# goodfet42.net
KiCad netlist of a schematic drawn in EAGLE
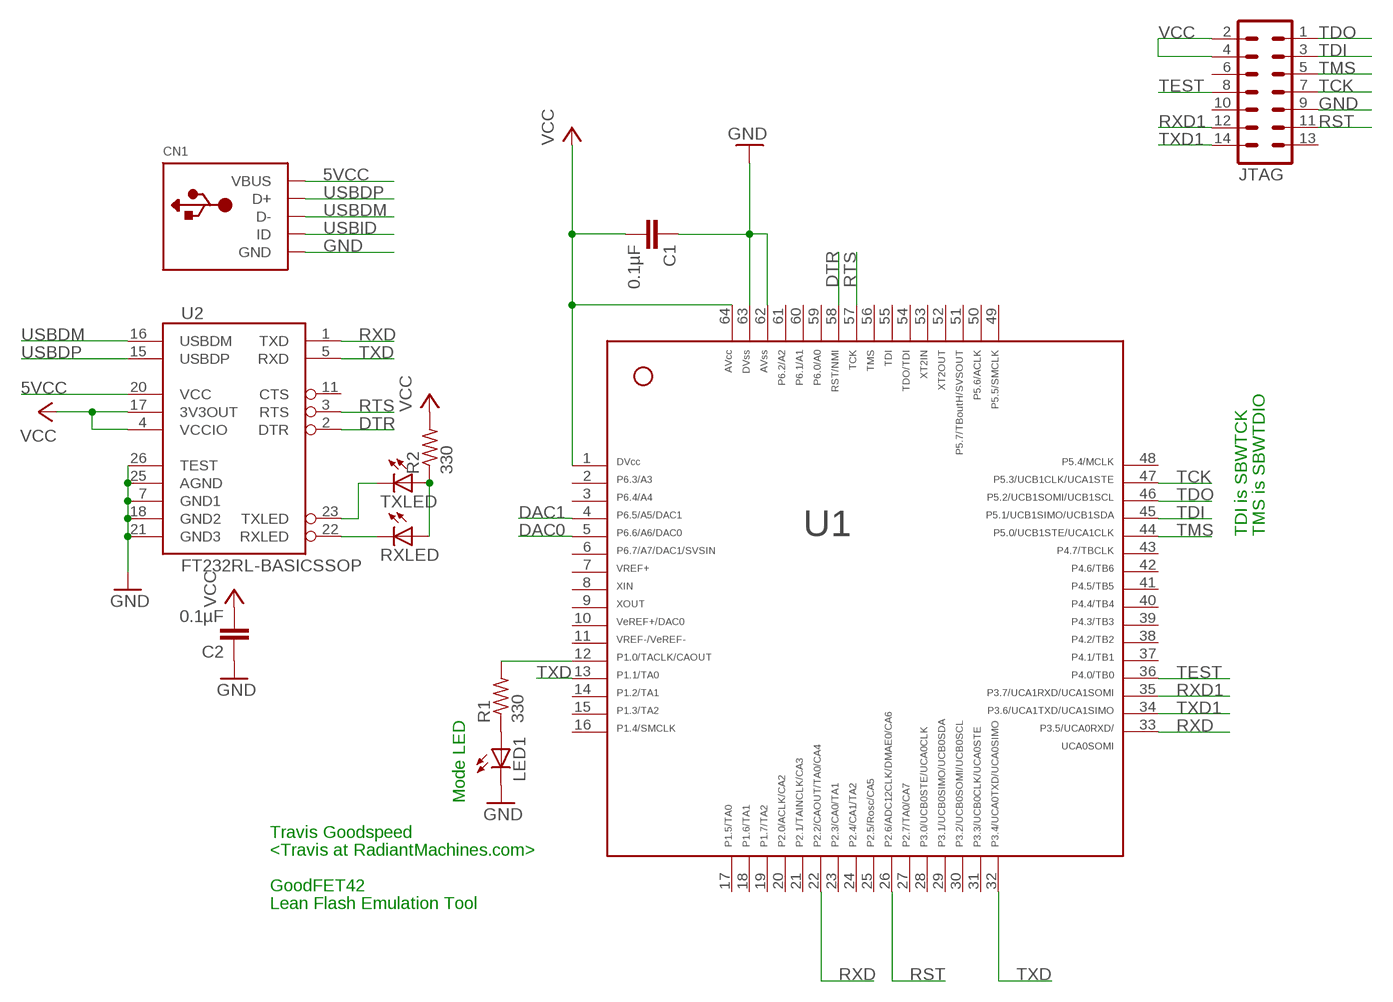
[diagram p0: schematic, sheet 1]

(export (version "E")
  (design (tool "Eeschema 10.0.6"))
  (components
    (comp (ref "C1")
      (value "0.1µF")
      (footprint "eagle-import:C0603")
      (libsource (lib "eagle-import") (part "C-EUC0603"))
    )
    (comp (ref "C2")
      (value "0.1µF")
      (footprint "eagle-import:C0603")
      (libsource (lib "eagle-import") (part "C-EUC0603"))
    )
    (comp (ref "CN1")
      (value "USBMINIB")
      (footprint "eagle-import:USB-MINIB")
      (libsource (lib "eagle-import") (part "USBMINIB"))
    )
    (comp (ref "JTAG")
      (value "MA07-2")
      (footprint "eagle-import:MA07-2")
      (libsource (lib "eagle-import") (part "MA07-2"))
    )
    (comp (ref "LED1")
      (value "LEDCHIP-LED0603")
      (footprint "eagle-import:CHIP-LED0603")
      (libsource (lib "eagle-import") (part "LEDCHIP-LED0603"))
    )
    (comp (ref "R1")
      (value "330")
      (footprint "eagle-import:R0603")
      (libsource (lib "eagle-import") (part "R-US_R0603"))
    )
    (comp (ref "R2")
      (value "330")
      (footprint "eagle-import:R0603")
      (libsource (lib "eagle-import") (part "R-US_R0603"))
    )
    (comp (ref "RXLED")
      (value "LEDCHIP-LED0603")
      (footprint "eagle-import:CHIP-LED0603")
      (libsource (lib "eagle-import") (part "LEDCHIP-LED0603"))
    )
    (comp (ref "TXLED")
      (value "LEDCHIP-LED0603")
      (footprint "eagle-import:CHIP-LED0603")
      (libsource (lib "eagle-import") (part "LEDCHIP-LED0603"))
    )
    (comp (ref "U1")
      (value "F261X---PM64")
      (footprint "eagle-import:PM_PAG64")
      (libsource (lib "eagle-import") (part "F261X---PM64"))
    )
    (comp (ref "U2")
      (value "FT232RL-BASICSSOP")
      (footprint "eagle-import:SSOP28DB")
      (libsource (lib "eagle-import") (part "FT232RL-BASICSSOP"))
    )
  )
  (nets
    (net (code "1") (name "/5VCC") (class "Default")
      (node (ref "CN1") (pin "VBUS") (pinfunction "VBUS_VBUS") (pintype "power_in"))
      (node (ref "U2") (pin "20") (pinfunction "VCC_20") (pintype "power_in"))
    )
    (net (code "2") (name "/DAC0") (class "Default")
      (node (ref "U1") (pin "5") (pinfunction "5_5") (pintype "bidirectional"))
    )
    (net (code "3") (name "/DAC1") (class "Default")
      (node (ref "U1") (pin "4") (pinfunction "4_4") (pintype "bidirectional"))
    )
    (net (code "4") (name "/DTR") (class "Default")
      (node (ref "U1") (pin "58") (pinfunction "58_58") (pintype "input"))
      (node (ref "U2") (pin "2") (pinfunction "DTR_2") (pintype "bidirectional"))
    )
    (net (code "5") (name "/RST") (class "Default")
      (node (ref "JTAG") (pin "11") (pinfunction "11_11") (pintype "passive"))
      (node (ref "U1") (pin "26") (pinfunction "26_26") (pintype "bidirectional"))
    )
    (net (code "6") (name "/RTS") (class "Default")
      (node (ref "U1") (pin "57") (pinfunction "57_57") (pintype "input"))
      (node (ref "U2") (pin "3") (pinfunction "RTS_3") (pintype "bidirectional"))
    )
    (net (code "7") (name "/RXD") (class "Default")
      (node (ref "U1") (pin "22") (pinfunction "22_22") (pintype "bidirectional"))
      (node (ref "U1") (pin "33") (pinfunction "33_33") (pintype "bidirectional"))
      (node (ref "U2") (pin "1") (pinfunction "TXD_1") (pintype "output"))
    )
    (net (code "8") (name "/RXD1") (class "Default")
      (node (ref "JTAG") (pin "12") (pinfunction "12_12") (pintype "passive"))
      (node (ref "U1") (pin "35") (pinfunction "35_35") (pintype "bidirectional"))
    )
    (net (code "9") (name "/TCK") (class "Default")
      (node (ref "JTAG") (pin "7") (pinfunction "7_7") (pintype "passive"))
      (node (ref "U1") (pin "47") (pinfunction "47_47") (pintype "bidirectional"))
    )
    (net (code "10") (name "/TDI") (class "Default")
      (node (ref "JTAG") (pin "3") (pinfunction "3_3") (pintype "passive"))
      (node (ref "U1") (pin "45") (pinfunction "45_45") (pintype "bidirectional"))
    )
    (net (code "11") (name "/TDO") (class "Default")
      (node (ref "JTAG") (pin "1") (pinfunction "1_1") (pintype "passive"))
      (node (ref "U1") (pin "46") (pinfunction "46_46") (pintype "bidirectional"))
    )
    (net (code "12") (name "/TEST") (class "Default")
      (node (ref "JTAG") (pin "8") (pinfunction "8_8") (pintype "passive"))
      (node (ref "U1") (pin "36") (pinfunction "36_36") (pintype "output"))
    )
    (net (code "13") (name "/TMS") (class "Default")
      (node (ref "JTAG") (pin "5") (pinfunction "5_5") (pintype "passive"))
      (node (ref "U1") (pin "44") (pinfunction "44_44") (pintype "bidirectional"))
    )
    (net (code "14") (name "/TXD") (class "Default")
      (node (ref "U1") (pin "13") (pinfunction "13_13") (pintype "bidirectional"))
      (node (ref "U1") (pin "32") (pinfunction "32_32") (pintype "bidirectional"))
      (node (ref "U2") (pin "5") (pinfunction "RXD_5") (pintype "input"))
    )
    (net (code "15") (name "/TXD1") (class "Default")
      (node (ref "JTAG") (pin "14") (pinfunction "14_14") (pintype "passive"))
      (node (ref "U1") (pin "34") (pinfunction "34_34") (pintype "bidirectional"))
    )
    (net (code "16") (name "/USBDM") (class "Default")
      (node (ref "CN1") (pin "D-") (pinfunction "D-_D-") (pintype "bidirectional"))
      (node (ref "U2") (pin "16") (pinfunction "USBDM_16") (pintype "bidirectional"))
    )
    (net (code "17") (name "/USBDP") (class "Default")
      (node (ref "CN1") (pin "D+") (pinfunction "D+_D+") (pintype "bidirectional"))
      (node (ref "U2") (pin "15") (pinfunction "USBDP_15") (pintype "bidirectional"))
    )
    (net (code "18") (name "/USBID") (class "Default")
      (node (ref "CN1") (pin "ID") (pinfunction "ID_ID") (pintype "bidirectional"))
    )
    (net (code "19") (name "GND") (class "Default")
      (node (ref "C1") (pin "1") (pinfunction "1_1") (pintype "passive"))
      (node (ref "C2") (pin "1") (pinfunction "1_1") (pintype "passive"))
      (node (ref "CN1") (pin "GND") (pinfunction "GND_GND") (pintype "power_in"))
      (node (ref "JTAG") (pin "9") (pinfunction "9_9") (pintype "passive"))
      (node (ref "LED1") (pin "C") (pinfunction "C_C") (pintype "passive"))
      (node (ref "U1") (pin "62") (pinfunction "62_62") (pintype "power_in"))
      (node (ref "U1") (pin "63") (pinfunction "63_63") (pintype "power_in"))
      (node (ref "U2") (pin "18") (pinfunction "GND2_18") (pintype "power_in"))
      (node (ref "U2") (pin "21") (pinfunction "GND3_21") (pintype "power_in"))
      (node (ref "U2") (pin "25") (pinfunction "AGND_25") (pintype "power_in"))
      (node (ref "U2") (pin "26") (pinfunction "TEST_26") (pintype "input"))
      (node (ref "U2") (pin "7") (pinfunction "GND1_7") (pintype "power_in"))
    )
    (net (code "20") (name "Net-(LED1-PadA)") (class "Default")
      (node (ref "LED1") (pin "A") (pinfunction "A_A") (pintype "passive"))
      (node (ref "R1") (pin "1") (pinfunction "1_1") (pintype "passive"))
    )
    (net (code "21") (name "Net-(R1-Pad2)") (class "Default")
      (node (ref "R1") (pin "2") (pinfunction "2_2") (pintype "passive"))
      (node (ref "U1") (pin "12") (pinfunction "12_12") (pintype "bidirectional"))
    )
    (net (code "22") (name "Net-(R2-Pad1)") (class "Default")
      (node (ref "R2") (pin "1") (pinfunction "1_1") (pintype "passive"))
      (node (ref "RXLED") (pin "A") (pinfunction "A_A") (pintype "passive"))
      (node (ref "TXLED") (pin "A") (pinfunction "A_A") (pintype "passive"))
    )
    (net (code "23") (name "Net-(U2-RXLED)") (class "Default")
      (node (ref "RXLED") (pin "C") (pinfunction "C_C") (pintype "passive"))
      (node (ref "U2") (pin "22") (pinfunction "RXLED_22") (pintype "bidirectional"))
    )
    (net (code "24") (name "Net-(U2-TXLED)") (class "Default")
      (node (ref "TXLED") (pin "C") (pinfunction "C_C") (pintype "passive"))
      (node (ref "U2") (pin "23") (pinfunction "TXLED_23") (pintype "bidirectional"))
    )
    (net (code "25") (name "VCC") (class "Default")
      (node (ref "C1") (pin "2") (pinfunction "2_2") (pintype "passive"))
      (node (ref "C2") (pin "2") (pinfunction "2_2") (pintype "passive"))
      (node (ref "JTAG") (pin "2") (pinfunction "2_2") (pintype "passive"))
      (node (ref "JTAG") (pin "4") (pinfunction "4_4") (pintype "passive"))
      (node (ref "R2") (pin "2") (pinfunction "2_2") (pintype "passive"))
      (node (ref "U1") (pin "1") (pinfunction "1_1") (pintype "power_in"))
      (node (ref "U1") (pin "64") (pinfunction "64_64") (pintype "power_in"))
      (node (ref "U2") (pin "17") (pinfunction "3V3OUT_17") (pintype "output"))
      (node (ref "U2") (pin "4") (pinfunction "VCCIO_4") (pintype "power_in"))
    )
    (net (code "26") (name "unconnected-(JTAG-Pad6)") (class "Default")
      (node (ref "JTAG") (pin "6") (pinfunction "6_6") (pintype "passive"))
    )
    (net (code "27") (name "unconnected-(JTAG-Pad10)") (class "Default")
      (node (ref "JTAG") (pin "10") (pinfunction "10_10") (pintype "passive"))
    )
    (net (code "28") (name "unconnected-(JTAG-Pad13)") (class "Default")
      (node (ref "JTAG") (pin "13") (pinfunction "13_13") (pintype "passive"))
    )
    (net (code "29") (name "unconnected-(U1-Pad2)") (class "Default")
      (node (ref "U1") (pin "2") (pinfunction "2_2") (pintype "bidirectional"))
    )
    (net (code "30") (name "unconnected-(U1-Pad3)") (class "Default")
      (node (ref "U1") (pin "3") (pinfunction "3_3") (pintype "bidirectional"))
    )
    (net (code "31") (name "unconnected-(U1-Pad6)") (class "Default")
      (node (ref "U1") (pin "6") (pinfunction "6_6") (pintype "bidirectional"))
    )
    (net (code "32") (name "unconnected-(U1-Pad7)") (class "Default")
      (node (ref "U1") (pin "7") (pinfunction "7_7") (pintype "output"))
    )
    (net (code "33") (name "unconnected-(U1-Pad8)") (class "Default")
      (node (ref "U1") (pin "8") (pinfunction "8_8") (pintype "input"))
    )
    (net (code "34") (name "unconnected-(U1-Pad9)") (class "Default")
      (node (ref "U1") (pin "9") (pinfunction "9_9") (pintype "output"))
    )
    (net (code "35") (name "unconnected-(U1-Pad10)") (class "Default")
      (node (ref "U1") (pin "10") (pinfunction "10_10") (pintype "bidirectional"))
    )
    (net (code "36") (name "unconnected-(U1-Pad11)") (class "Default")
      (node (ref "U1") (pin "11") (pinfunction "11_11") (pintype "bidirectional"))
    )
    (net (code "37") (name "unconnected-(U1-Pad14)") (class "Default")
      (node (ref "U1") (pin "14") (pinfunction "14_14") (pintype "bidirectional"))
    )
    (net (code "38") (name "unconnected-(U1-Pad15)") (class "Default")
      (node (ref "U1") (pin "15") (pinfunction "15_15") (pintype "bidirectional"))
    )
    (net (code "39") (name "unconnected-(U1-Pad16)") (class "Default")
      (node (ref "U1") (pin "16") (pinfunction "16_16") (pintype "bidirectional"))
    )
    (net (code "40") (name "unconnected-(U1-Pad17)") (class "Default")
      (node (ref "U1") (pin "17") (pinfunction "17_17") (pintype "bidirectional"))
    )
    (net (code "41") (name "unconnected-(U1-Pad18)") (class "Default")
      (node (ref "U1") (pin "18") (pinfunction "18_18") (pintype "bidirectional"))
    )
    (net (code "42") (name "unconnected-(U1-Pad19)") (class "Default")
      (node (ref "U1") (pin "19") (pinfunction "19_19") (pintype "bidirectional"))
    )
    (net (code "43") (name "unconnected-(U1-Pad20)") (class "Default")
      (node (ref "U1") (pin "20") (pinfunction "20_20") (pintype "bidirectional"))
    )
    (net (code "44") (name "unconnected-(U1-Pad21)") (class "Default")
      (node (ref "U1") (pin "21") (pinfunction "21_21") (pintype "bidirectional"))
    )
    (net (code "45") (name "unconnected-(U1-Pad23)") (class "Default")
      (node (ref "U1") (pin "23") (pinfunction "23_23") (pintype "bidirectional"))
    )
    (net (code "46") (name "unconnected-(U1-Pad24)") (class "Default")
      (node (ref "U1") (pin "24") (pinfunction "24_24") (pintype "bidirectional"))
    )
    (net (code "47") (name "unconnected-(U1-Pad25)") (class "Default")
      (node (ref "U1") (pin "25") (pinfunction "25_25") (pintype "bidirectional"))
    )
    (net (code "48") (name "unconnected-(U1-Pad27)") (class "Default")
      (node (ref "U1") (pin "27") (pinfunction "27_27") (pintype "bidirectional"))
    )
    (net (code "49") (name "unconnected-(U1-Pad28)") (class "Default")
      (node (ref "U1") (pin "28") (pinfunction "28_28") (pintype "bidirectional"))
    )
    (net (code "50") (name "unconnected-(U1-Pad29)") (class "Default")
      (node (ref "U1") (pin "29") (pinfunction "29_29") (pintype "bidirectional"))
    )
    (net (code "51") (name "unconnected-(U1-Pad30)") (class "Default")
      (node (ref "U1") (pin "30") (pinfunction "30_30") (pintype "bidirectional"))
    )
    (net (code "52") (name "unconnected-(U1-Pad31)") (class "Default")
      (node (ref "U1") (pin "31") (pinfunction "31_31") (pintype "bidirectional"))
    )
    (net (code "53") (name "unconnected-(U1-Pad37)") (class "Default")
      (node (ref "U1") (pin "37") (pinfunction "37_37") (pintype "bidirectional"))
    )
    (net (code "54") (name "unconnected-(U1-Pad38)") (class "Default")
      (node (ref "U1") (pin "38") (pinfunction "38_38") (pintype "bidirectional"))
    )
    (net (code "55") (name "unconnected-(U1-Pad39)") (class "Default")
      (node (ref "U1") (pin "39") (pinfunction "39_39") (pintype "bidirectional"))
    )
    (net (code "56") (name "unconnected-(U1-Pad40)") (class "Default")
      (node (ref "U1") (pin "40") (pinfunction "40_40") (pintype "input"))
    )
    (net (code "57") (name "unconnected-(U1-Pad41)") (class "Default")
      (node (ref "U1") (pin "41") (pinfunction "41_41") (pintype "bidirectional"))
    )
    (net (code "58") (name "unconnected-(U1-Pad42)") (class "Default")
      (node (ref "U1") (pin "42") (pinfunction "42_42") (pintype "bidirectional"))
    )
    (net (code "59") (name "unconnected-(U1-Pad43)") (class "Default")
      (node (ref "U1") (pin "43") (pinfunction "43_43") (pintype "bidirectional"))
    )
    (net (code "60") (name "unconnected-(U1-Pad48)") (class "Default")
      (node (ref "U1") (pin "48") (pinfunction "48_48") (pintype "bidirectional"))
    )
    (net (code "61") (name "unconnected-(U1-Pad49)") (class "Default")
      (node (ref "U1") (pin "49") (pinfunction "49_49") (pintype "bidirectional"))
    )
    (net (code "62") (name "unconnected-(U1-Pad50)") (class "Default")
      (node (ref "U1") (pin "50") (pinfunction "50_50") (pintype "bidirectional"))
    )
    (net (code "63") (name "unconnected-(U1-Pad51)") (class "Default")
      (node (ref "U1") (pin "51") (pinfunction "51_51") (pintype "bidirectional"))
    )
    (net (code "64") (name "unconnected-(U1-Pad52)") (class "Default")
      (node (ref "U1") (pin "52") (pinfunction "52_52") (pintype "output"))
    )
    (net (code "65") (name "unconnected-(U1-Pad53)") (class "Default")
      (node (ref "U1") (pin "53") (pinfunction "53_53") (pintype "input"))
    )
    (net (code "66") (name "unconnected-(U1-Pad54)") (class "Default")
      (node (ref "U1") (pin "54") (pinfunction "54_54") (pintype "bidirectional"))
    )
    (net (code "67") (name "unconnected-(U1-Pad55)") (class "Default")
      (node (ref "U1") (pin "55") (pinfunction "55_55") (pintype "input"))
    )
    (net (code "68") (name "unconnected-(U1-Pad56)") (class "Default")
      (node (ref "U1") (pin "56") (pinfunction "56_56") (pintype "input"))
    )
    (net (code "69") (name "unconnected-(U1-Pad59)") (class "Default")
      (node (ref "U1") (pin "59") (pinfunction "59_59") (pintype "bidirectional"))
    )
    (net (code "70") (name "unconnected-(U1-Pad60)") (class "Default")
      (node (ref "U1") (pin "60") (pinfunction "60_60") (pintype "bidirectional"))
    )
    (net (code "71") (name "unconnected-(U1-Pad61)") (class "Default")
      (node (ref "U1") (pin "61") (pinfunction "61_61") (pintype "bidirectional"))
    )
    (net (code "72") (name "unconnected-(U2-CTS-Pad11)") (class "Default")
      (node (ref "U2") (pin "11") (pinfunction "CTS_11") (pintype "bidirectional"))
    )
  )
)
